# NU1680_Rx_EVM_SCH_Ver_2.net
KiCad netlist of a schematic drawn in Altium Designer
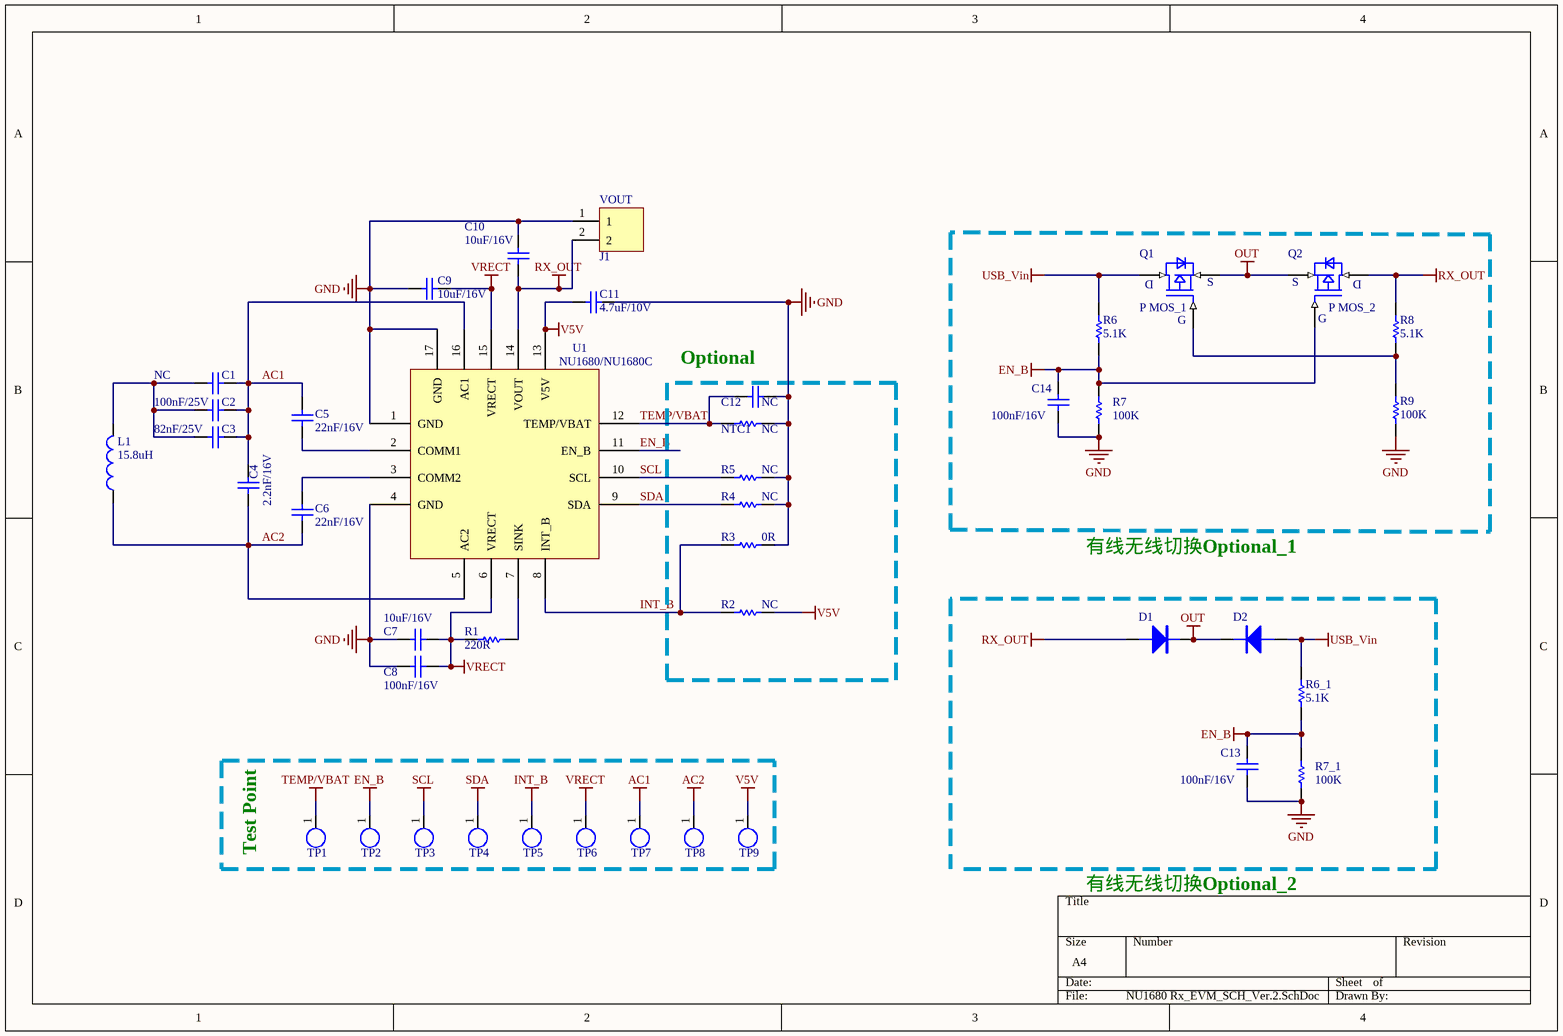
[diagram p0: NU1680 Rx_EVM_SCH_Ver.2.SchDoc]

(export (version "E")
  (design (tool "Eeschema 10.0.6"))
  (components
    (comp (ref "C1")
      (value "NC")
      (footprint "SMD_R5_CAP_0402")
      (description "0402")
      (libsource (lib "LL&S library") (part "cap"))
    )
    (comp (ref "C2")
      (value "100nF/25V")
      (footprint "SMD_R5_CAP_0402")
      (description "0402")
      (libsource (lib "LL&S library") (part "cap"))
    )
    (comp (ref "C3")
      (value "82nF/25V")
      (footprint "SMD_R5_CAP_0402")
      (description "0402")
      (libsource (lib "LL&S library") (part "cap"))
    )
    (comp (ref "C4")
      (value "2.2nF/16V")
      (footprint "SMD_R5_CAP_0402")
      (description "0402")
      (libsource (lib "LL&S library") (part "cap"))
    )
    (comp (ref "C5")
      (value "22nF/16V")
      (footprint "SMD_R5_CAP_0402")
      (description "0402")
      (libsource (lib "LL&S library") (part "cap"))
    )
    (comp (ref "C6")
      (value "22nF/16V")
      (footprint "SMD_R5_CAP_0402")
      (description "0402")
      (libsource (lib "LL&S library") (part "cap"))
    )
    (comp (ref "C7")
      (value "10uF/16V")
      (footprint "SMD_R5_CAP_0603")
      (description "0603")
      (libsource (lib "LL&S library") (part "cap"))
    )
    (comp (ref "C8")
      (value "100nF/16V")
      (footprint "SMD_R5_CAP_0402")
      (description "0402")
      (libsource (lib "LL&S library") (part "cap"))
    )
    (comp (ref "C9")
      (value "10uF/16V")
      (footprint "SMD_R5_CAP_0603")
      (description "0603")
      (libsource (lib "LL&S library") (part "cap"))
    )
    (comp (ref "C10")
      (value "10uF/16V")
      (footprint "SMD_R5_CAP_0603")
      (description "0603")
      (libsource (lib "LL&S library") (part "cap"))
    )
    (comp (ref "C11")
      (value "4.7uF/10V")
      (footprint "SMD_R5_CAP_0603")
      (description "0603")
      (libsource (lib "LL&S library") (part "cap"))
    )
    (comp (ref "C12")
      (value "NC")
      (footprint "SMD_R5_CAP_0402")
      (description "0402")
      (libsource (lib "LL&S library") (part "cap"))
    )
    (comp (ref "C13")
      (value "100nF/16V")
      (footprint "SMD_R5_CAP_0402")
      (description "0402")
      (libsource (lib "LL&S library") (part "cap"))
    )
    (comp (ref "C14")
      (value "100nF/16V")
      (footprint "SMD_R5_CAP_0402")
      (description "0402")
      (libsource (lib "LL&S library") (part "cap"))
    )
    (comp (ref "D1")
      (value "~")
      (footprint "DO-201AD(V)")
      (description "Diode")
      (libsource (lib "60W FAN6921MR LED Power schlib") (part "DIODE"))
    )
    (comp (ref "D2")
      (value "~")
      (footprint "DO-201AD(V)")
      (description "Diode")
      (libsource (lib "60W FAN6921MR LED Power schlib") (part "DIODE"))
    )
    (comp (ref "L1") (value "15.8uH") (footprint "HDR1X2") (libsource (lib "LL&S library") (part "Inductor")))
    (comp (ref "NTC1")
      (value "NC")
      (footprint "SMD_R5_RES_0402")
      (description "0402")
      (libsource (lib "LL&S library") (part "Res1"))
    )
    (comp (ref "Q1") (value "P MOS_1") (libsource (lib "60W FAN6921MR LED Power schlib") (part "P MOS_1")))
    (comp (ref "Q2") (value "P MOS_2") (libsource (lib "60W FAN6921MR LED Power schlib") (part "P MOS_2")))
    (comp (ref "R1")
      (value "220R")
      (footprint "SMD_R5_RES_0805")
      (description "0805")
      (libsource (lib "LL&S library") (part "Res1"))
    )
    (comp (ref "R2")
      (value "NC")
      (footprint "SMD_R5_RES_0402")
      (description "0402")
      (libsource (lib "LL&S library") (part "Res1"))
    )
    (comp (ref "R3")
      (value "0R")
      (footprint "SMD_R5_RES_0402")
      (description "0402")
      (libsource (lib "LL&S library") (part "Res1"))
    )
    (comp (ref "R4")
      (value "NC")
      (footprint "SMD_R5_RES_0402")
      (description "0402")
      (libsource (lib "LL&S library") (part "Res1"))
    )
    (comp (ref "R5")
      (value "NC")
      (footprint "SMD_R5_RES_0402")
      (description "0402")
      (libsource (lib "LL&S library") (part "Res1"))
    )
    (comp (ref "R6")
      (value "5.1K")
      (footprint "IR0402(R)")
      (description "RES 1.8Kohm 1/16W 1% 0402")
      (fields (field (name "Comment") "1.8K/5%/0402") (field (name "PUBLISHER") "Altium Limited"))
      (libsource (lib "PCB_Project1") (part "Res1"))
    )
    (comp (ref "R6_1")
      (value "5.1K")
      (footprint "IR0402(R)")
      (description "RES 1.8Kohm 1/16W 1% 0402")
      (fields (field (name "Comment") "1.8K/5%/0402") (field (name "PUBLISHER") "Altium Limited"))
      (libsource (lib "PCB_Project1") (part "Res1"))
    )
    (comp (ref "R7")
      (value "100K")
      (footprint "IR0402(R)")
      (description "RES 1.8Kohm 1/16W 1% 0402")
      (fields (field (name "Comment") "1.8K/5%/0402") (field (name "PUBLISHER") "Altium Limited"))
      (libsource (lib "PCB_Project1") (part "Res1"))
    )
    (comp (ref "R7_1")
      (value "100K")
      (footprint "IR0402(R)")
      (description "RES 1.8Kohm 1/16W 1% 0402")
      (fields (field (name "Comment") "1.8K/5%/0402") (field (name "PUBLISHER") "Altium Limited"))
      (libsource (lib "PCB_Project1") (part "Res1"))
    )
    (comp (ref "R8")
      (value "5.1K")
      (footprint "IR0402(R)")
      (description "RES 1.8Kohm 1/16W 1% 0402")
      (fields (field (name "Comment") "1.8K/5%/0402") (field (name "PUBLISHER") "Altium Limited"))
      (libsource (lib "PCB_Project1") (part "Res1"))
    )
    (comp (ref "R9")
      (value "100K")
      (footprint "IR0402(R)")
      (description "RES 1.8Kohm 1/16W 1% 0402")
      (fields (field (name "Comment") "1.8K/5%/0402") (field (name "PUBLISHER") "Altium Limited"))
      (libsource (lib "PCB_Project1") (part "Res1"))
    )
    (comp (ref "TP1")
      (value "~")
      (footprint "SMD_R5_Testpoint_1.5mm")
      (libsource (lib "LL&S library") (part "Testpoint"))
    )
    (comp (ref "TP2")
      (value "~")
      (footprint "SMD_R5_Testpoint_1.5mm")
      (libsource (lib "LL&S library") (part "Testpoint"))
    )
    (comp (ref "TP3")
      (value "~")
      (footprint "SMD_R5_Testpoint_1.5mm")
      (libsource (lib "LL&S library") (part "Testpoint"))
    )
    (comp (ref "TP4")
      (value "~")
      (footprint "SMD_R5_Testpoint_1.5mm")
      (libsource (lib "LL&S library") (part "Testpoint"))
    )
    (comp (ref "TP5")
      (value "~")
      (footprint "SMD_R5_Testpoint_1.5mm")
      (libsource (lib "LL&S library") (part "Testpoint"))
    )
    (comp (ref "TP6")
      (value "~")
      (footprint "SMD_R5_Testpoint_1.5mm")
      (libsource (lib "LL&S library") (part "Testpoint"))
    )
    (comp (ref "TP7")
      (value "~")
      (footprint "SMD_R5_Testpoint_1.5mm")
      (libsource (lib "LL&S library") (part "Testpoint"))
    )
    (comp (ref "TP8")
      (value "~")
      (footprint "SMD_R5_Testpoint_1.5mm")
      (libsource (lib "LL&S library") (part "Testpoint"))
    )
    (comp (ref "TP9")
      (value "~")
      (footprint "SMD_R5_Testpoint_1.5mm")
      (libsource (lib "LL&S library") (part "Testpoint"))
    )
    (comp (ref "U1")
      (value "NU1680/NU1680C")
      (footprint "NU1680_QFN16")
      (libsource (lib "LZJ_Schlib") (part "NU1680"))
    )
    (comp (ref "VOUT") (value "J1") (libsource (lib "LL&S library") (part "CONNECT2X1")))
  )
  (nets
    (net (code "1") (name "AC1") (class "Default")
      (node (ref "C1") (pin "2") (pinfunction "2_2") (pintype "passive"))
      (node (ref "C2") (pin "2") (pinfunction "2_2") (pintype "passive"))
      (node (ref "C3") (pin "2") (pinfunction "2_2") (pintype "passive"))
      (node (ref "C4") (pin "2") (pinfunction "2_2") (pintype "passive"))
      (node (ref "C5") (pin "1") (pinfunction "1_1") (pintype "passive"))
      (node (ref "TP7") (pin "1") (pinfunction "1_1") (pintype "passive"))
      (node (ref "U1") (pin "16") (pinfunction "AC1_16") (pintype "passive"))
    )
    (net (code "2") (name "AC2") (class "Default")
      (node (ref "C4") (pin "1") (pinfunction "1_1") (pintype "passive"))
      (node (ref "C6") (pin "1") (pinfunction "1_1") (pintype "passive"))
      (node (ref "L1") (pin "1") (pinfunction "1_1") (pintype "passive"))
      (node (ref "TP8") (pin "1") (pinfunction "1_1") (pintype "passive"))
      (node (ref "U1") (pin "5") (pinfunction "AC2_5") (pintype "passive"))
    )
    (net (code "3") (name "EN_B") (class "Default")
      (node (ref "C13") (pin "1") (pinfunction "1_1") (pintype "passive"))
      (node (ref "C14") (pin "1") (pinfunction "1_1") (pintype "passive"))
      (node (ref "Q2") (pin "1") (pinfunction "G_1") (pintype "input"))
      (node (ref "R6") (pin "1") (pinfunction "1_1") (pintype "passive"))
      (node (ref "R6_1") (pin "1") (pinfunction "1_1") (pintype "passive"))
      (node (ref "R7") (pin "2") (pinfunction "2_2") (pintype "passive"))
      (node (ref "R7_1") (pin "2") (pinfunction "2_2") (pintype "passive"))
      (node (ref "TP2") (pin "1") (pinfunction "1_1") (pintype "passive"))
      (node (ref "U1") (pin "11") (pinfunction "EN_B_11") (pintype "passive"))
    )
    (net (code "4") (name "GND") (class "Default")
      (node (ref "C10") (pin "2") (pinfunction "2_2") (pintype "passive"))
      (node (ref "C11") (pin "2") (pinfunction "2_2") (pintype "passive"))
      (node (ref "C12") (pin "1") (pinfunction "1_1") (pintype "passive"))
      (node (ref "C13") (pin "2") (pinfunction "2_2") (pintype "passive"))
      (node (ref "C14") (pin "2") (pinfunction "2_2") (pintype "passive"))
      (node (ref "C7") (pin "2") (pinfunction "2_2") (pintype "passive"))
      (node (ref "C8") (pin "2") (pinfunction "2_2") (pintype "passive"))
      (node (ref "C9") (pin "2") (pinfunction "2_2") (pintype "passive"))
      (node (ref "NTC1") (pin "1") (pinfunction "1_1") (pintype "passive"))
      (node (ref "R3") (pin "2") (pinfunction "2_2") (pintype "passive"))
      (node (ref "R4") (pin "1") (pinfunction "1_1") (pintype "passive"))
      (node (ref "R5") (pin "1") (pinfunction "1_1") (pintype "passive"))
      (node (ref "R7") (pin "1") (pinfunction "1_1") (pintype "passive"))
      (node (ref "R7_1") (pin "1") (pinfunction "1_1") (pintype "passive"))
      (node (ref "R9") (pin "2") (pinfunction "2_2") (pintype "passive"))
      (node (ref "U1") (pin "1") (pinfunction "GND_1") (pintype "passive"))
      (node (ref "U1") (pin "17") (pinfunction "GND_17") (pintype "passive"))
      (node (ref "U1") (pin "4") (pinfunction "GND_4") (pintype "passive"))
      (node (ref "VOUT") (pin "1") (pinfunction "1_1") (pintype "passive"))
    )
    (net (code "5") (name "INT_B") (class "Default")
      (node (ref "R2") (pin "1") (pinfunction "1_1") (pintype "passive"))
      (node (ref "R3") (pin "1") (pinfunction "1_1") (pintype "passive"))
      (node (ref "TP5") (pin "1") (pinfunction "1_1") (pintype "passive"))
      (node (ref "U1") (pin "8") (pinfunction "INT_B_8") (pintype "passive"))
    )
    (net (code "6") (name "Net-(C1-Pad1)") (class "Default")
      (node (ref "C1") (pin "1") (pinfunction "1_1") (pintype "passive"))
      (node (ref "C2") (pin "1") (pinfunction "1_1") (pintype "passive"))
      (node (ref "C3") (pin "1") (pinfunction "1_1") (pintype "passive"))
      (node (ref "L1") (pin "2") (pinfunction "2_2") (pintype "passive"))
    )
    (net (code "7") (name "Net-(Q1-G)") (class "Default")
      (node (ref "Q1") (pin "1") (pinfunction "G_1") (pintype "input"))
      (node (ref "R8") (pin "2") (pinfunction "2_2") (pintype "passive"))
      (node (ref "R9") (pin "1") (pinfunction "1_1") (pintype "passive"))
    )
    (net (code "8") (name "Net-(U1-COMM1)") (class "Default")
      (node (ref "C5") (pin "2") (pinfunction "2_2") (pintype "passive"))
      (node (ref "U1") (pin "2") (pinfunction "COMM1_2") (pintype "passive"))
    )
    (net (code "9") (name "Net-(U1-COMM2)") (class "Default")
      (node (ref "C6") (pin "2") (pinfunction "2_2") (pintype "passive"))
      (node (ref "U1") (pin "3") (pinfunction "COMM2_3") (pintype "passive"))
    )
    (net (code "10") (name "Net-(U1-SINK)") (class "Default")
      (node (ref "R1") (pin "1") (pinfunction "1_1") (pintype "passive"))
      (node (ref "U1") (pin "7") (pinfunction "SINK_7") (pintype "passive"))
    )
    (net (code "11") (name "OUT") (class "Default")
      (node (ref "D1") (pin "2") (pinfunction "K_2") (pintype "passive"))
      (node (ref "D2") (pin "2") (pinfunction "K_2") (pintype "passive"))
      (node (ref "Q1") (pin "3") (pinfunction "S_3") (pintype "input"))
      (node (ref "Q2") (pin "2") (pinfunction "D_2") (pintype "input"))
    )
    (net (code "12") (name "RX_OUT") (class "Default")
      (node (ref "C10") (pin "1") (pinfunction "1_1") (pintype "passive"))
      (node (ref "D1") (pin "1") (pinfunction "A_1") (pintype "passive"))
      (node (ref "Q2") (pin "3") (pinfunction "S_3") (pintype "input"))
      (node (ref "R8") (pin "1") (pinfunction "1_1") (pintype "passive"))
      (node (ref "U1") (pin "14") (pinfunction "VOUT_14") (pintype "passive"))
      (node (ref "VOUT") (pin "2") (pinfunction "2_2") (pintype "passive"))
    )
    (net (code "13") (name "SCL") (class "Default")
      (node (ref "R5") (pin "2") (pinfunction "2_2") (pintype "passive"))
      (node (ref "TP3") (pin "1") (pinfunction "1_1") (pintype "passive"))
      (node (ref "U1") (pin "10") (pinfunction "SCL_10") (pintype "passive"))
    )
    (net (code "14") (name "SDA") (class "Default")
      (node (ref "R4") (pin "2") (pinfunction "2_2") (pintype "passive"))
      (node (ref "TP4") (pin "1") (pinfunction "1_1") (pintype "passive"))
      (node (ref "U1") (pin "9") (pinfunction "SDA_9") (pintype "passive"))
    )
    (net (code "15") (name "TEMP{slash}VBAT") (class "Default")
      (node (ref "C12") (pin "2") (pinfunction "2_2") (pintype "passive"))
      (node (ref "NTC1") (pin "2") (pinfunction "2_2") (pintype "passive"))
      (node (ref "TP1") (pin "1") (pinfunction "1_1") (pintype "passive"))
      (node (ref "U1") (pin "12") (pinfunction "TEMP/VBAT_12") (pintype "passive"))
    )
    (net (code "16") (name "USB_Vin") (class "Default")
      (node (ref "D2") (pin "1") (pinfunction "A_1") (pintype "passive"))
      (node (ref "Q1") (pin "2") (pinfunction "D_2") (pintype "input"))
      (node (ref "R6") (pin "2") (pinfunction "2_2") (pintype "passive"))
      (node (ref "R6_1") (pin "2") (pinfunction "2_2") (pintype "passive"))
    )
    (net (code "17") (name "V5V") (class "Default")
      (node (ref "C11") (pin "1") (pinfunction "1_1") (pintype "passive"))
      (node (ref "R2") (pin "2") (pinfunction "2_2") (pintype "passive"))
      (node (ref "TP9") (pin "1") (pinfunction "1_1") (pintype "passive"))
      (node (ref "U1") (pin "13") (pinfunction "V5V_13") (pintype "passive"))
    )
    (net (code "18") (name "VRECT") (class "Default")
      (node (ref "C7") (pin "1") (pinfunction "1_1") (pintype "passive"))
      (node (ref "C8") (pin "1") (pinfunction "1_1") (pintype "passive"))
      (node (ref "C9") (pin "1") (pinfunction "1_1") (pintype "passive"))
      (node (ref "R1") (pin "2") (pinfunction "2_2") (pintype "passive"))
      (node (ref "TP6") (pin "1") (pinfunction "1_1") (pintype "passive"))
      (node (ref "U1") (pin "15") (pinfunction "VRECT_15") (pintype "passive"))
      (node (ref "U1") (pin "6") (pinfunction "VRECT_6") (pintype "passive"))
    )
  )
)
